# light_scanner_v1_0.net
KiCad netlist of a schematic drawn in EAGLE
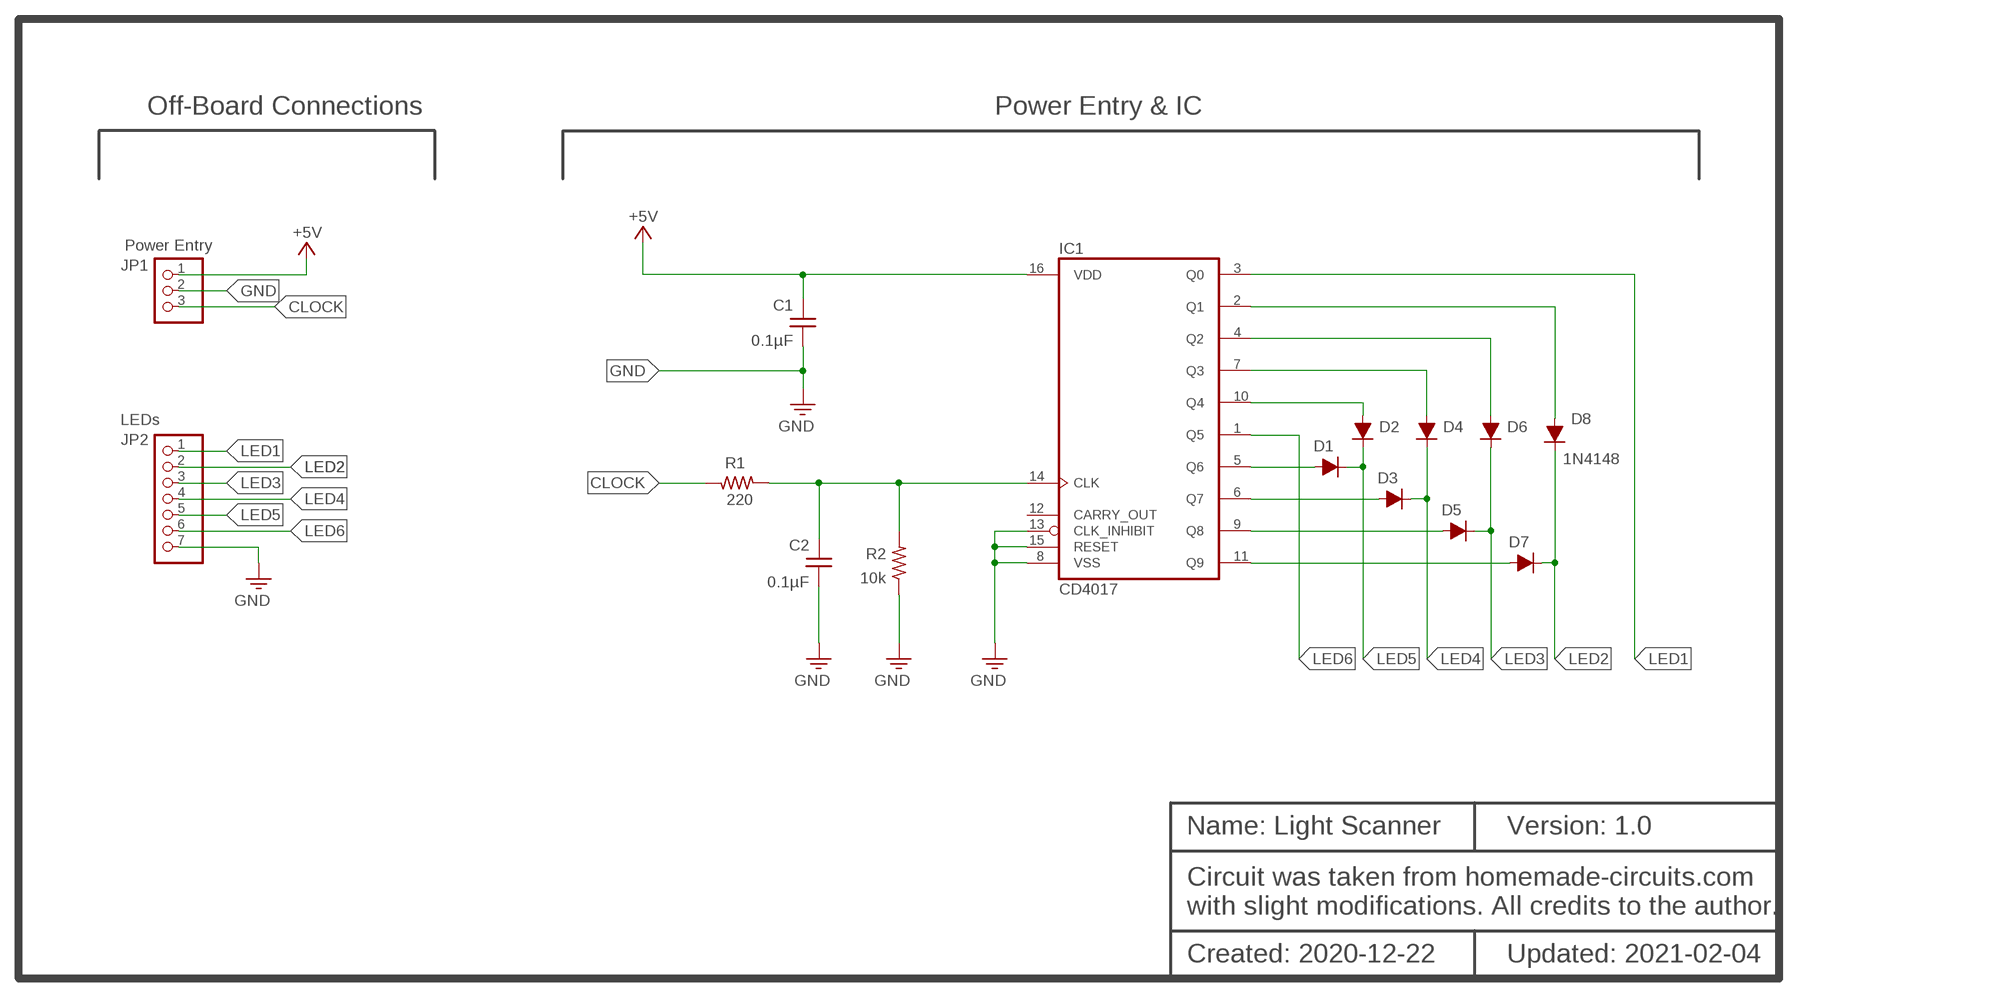
[diagram p0: schematic, sheet 1]

(export (version "E")
  (design (tool "Eeschema 10.0.6"))
  (components
    (comp (ref "C1")
      (value "0.1µF")
      (footprint "eagle-import:C_H5")
      (libsource (lib "eagle-import") (part "C_K104K15X7RF53H5_0.1µF"))
    )
    (comp (ref "C2")
      (value "0.1µF")
      (footprint "eagle-import:C_H5")
      (libsource (lib "eagle-import") (part "C_K104K15X7RF53H5_0.1µF"))
    )
    (comp (ref "D1")
      (value "D_1N4148")
      (footprint "eagle-import:DO35-7A")
      (libsource (lib "eagle-import") (part "D_1N4148"))
    )
    (comp (ref "D2")
      (value "D_1N4148")
      (footprint "eagle-import:DO35-7A")
      (libsource (lib "eagle-import") (part "D_1N4148"))
    )
    (comp (ref "D3")
      (value "D_1N4148")
      (footprint "eagle-import:DO35-7A")
      (libsource (lib "eagle-import") (part "D_1N4148"))
    )
    (comp (ref "D4")
      (value "D_1N4148")
      (footprint "eagle-import:DO35-7A")
      (libsource (lib "eagle-import") (part "D_1N4148"))
    )
    (comp (ref "D5")
      (value "D_1N4148")
      (footprint "eagle-import:DO35-7A")
      (libsource (lib "eagle-import") (part "D_1N4148"))
    )
    (comp (ref "D6")
      (value "D_1N4148")
      (footprint "eagle-import:DO35-7A")
      (libsource (lib "eagle-import") (part "D_1N4148"))
    )
    (comp (ref "D7")
      (value "D_1N4148")
      (footprint "eagle-import:DO35-7A")
      (libsource (lib "eagle-import") (part "D_1N4148"))
    )
    (comp (ref "D8")
      (value "1N4148")
      (footprint "eagle-import:DO35-7A")
      (libsource (lib "eagle-import") (part "D_1N4148"))
    )
    (comp (ref "IC1")
      (value "CD4017")
      (footprint "eagle-import:DIP16")
      (libsource (lib "eagle-import") (part "CD4017"))
    )
    (comp (ref "JP1")
      (value "Power Entry")
      (footprint "eagle-import:1X03")
      (libsource (lib "eagle-import") (part "PINHD-1X3"))
    )
    (comp (ref "JP2")
      (value "LEDs")
      (footprint "eagle-import:1X07")
      (libsource (lib "eagle-import") (part "PINHD-1X7"))
    )
    (comp (ref "R1")
      (value "220")
      (footprint "eagle-import:R_THM")
      (libsource (lib "eagle-import") (part "R_THM"))
    )
    (comp (ref "R2")
      (value "10k")
      (footprint "eagle-import:R_THM")
      (libsource (lib "eagle-import") (part "R_THM"))
    )
  )
  (nets
    (net (code "1") (name "+5V") (class "Default")
      (node (ref "C1") (pin "1") (pinfunction "1_1") (pintype "passive"))
      (node (ref "IC1") (pin "16") (pinfunction "VDD_16") (pintype "bidirectional"))
      (node (ref "JP1") (pin "1") (pinfunction "1_1") (pintype "passive"))
    )
    (net (code "2") (name "CLOCK") (class "Default")
      (node (ref "JP1") (pin "3") (pinfunction "3_3") (pintype "passive"))
      (node (ref "R1") (pin "2") (pinfunction "2_2") (pintype "passive"))
    )
    (net (code "3") (name "GND") (class "Default")
      (node (ref "C1") (pin "2") (pinfunction "2_2") (pintype "passive"))
      (node (ref "C2") (pin "2") (pinfunction "2_2") (pintype "passive"))
      (node (ref "IC1") (pin "13") (pinfunction "CLK_INHIBIT_13") (pintype "input"))
      (node (ref "IC1") (pin "15") (pinfunction "RESET_15") (pintype "input"))
      (node (ref "IC1") (pin "8") (pinfunction "VSS_8") (pintype "bidirectional"))
      (node (ref "JP1") (pin "2") (pinfunction "2_2") (pintype "passive"))
      (node (ref "JP2") (pin "7") (pinfunction "7_7") (pintype "passive"))
      (node (ref "R2") (pin "1") (pinfunction "1_1") (pintype "passive"))
    )
    (net (code "4") (name "LED1") (class "Default")
      (node (ref "IC1") (pin "3") (pinfunction "Q0_3") (pintype "output"))
      (node (ref "JP2") (pin "1") (pinfunction "1_1") (pintype "passive"))
    )
    (net (code "5") (name "LED2") (class "Default")
      (node (ref "D7") (pin "C") (pinfunction "C_C") (pintype "passive"))
      (node (ref "D8") (pin "C") (pinfunction "C_C") (pintype "passive"))
      (node (ref "JP2") (pin "2") (pinfunction "2_2") (pintype "passive"))
    )
    (net (code "6") (name "LED3") (class "Default")
      (node (ref "D5") (pin "C") (pinfunction "C_C") (pintype "passive"))
      (node (ref "D6") (pin "C") (pinfunction "C_C") (pintype "passive"))
      (node (ref "JP2") (pin "3") (pinfunction "3_3") (pintype "passive"))
    )
    (net (code "7") (name "LED4") (class "Default")
      (node (ref "D3") (pin "C") (pinfunction "C_C") (pintype "passive"))
      (node (ref "D4") (pin "C") (pinfunction "C_C") (pintype "passive"))
      (node (ref "JP2") (pin "4") (pinfunction "4_4") (pintype "passive"))
    )
    (net (code "8") (name "LED5") (class "Default")
      (node (ref "D1") (pin "C") (pinfunction "C_C") (pintype "passive"))
      (node (ref "D2") (pin "C") (pinfunction "C_C") (pintype "passive"))
      (node (ref "JP2") (pin "5") (pinfunction "5_5") (pintype "passive"))
    )
    (net (code "9") (name "LED6") (class "Default")
      (node (ref "IC1") (pin "1") (pinfunction "Q5_1") (pintype "output"))
      (node (ref "JP2") (pin "6") (pinfunction "6_6") (pintype "passive"))
    )
    (net (code "10") (name "Net-(IC1-CLK)") (class "Default")
      (node (ref "C2") (pin "1") (pinfunction "1_1") (pintype "passive"))
      (node (ref "IC1") (pin "14") (pinfunction "CLK_14") (pintype "input"))
      (node (ref "R1") (pin "1") (pinfunction "1_1") (pintype "passive"))
      (node (ref "R2") (pin "2") (pinfunction "2_2") (pintype "passive"))
    )
    (net (code "11") (name "Net-(IC1-Q1)") (class "Default")
      (node (ref "D8") (pin "A") (pinfunction "A_A") (pintype "passive"))
      (node (ref "IC1") (pin "2") (pinfunction "Q1_2") (pintype "output"))
    )
    (net (code "12") (name "Net-(IC1-Q2)") (class "Default")
      (node (ref "D6") (pin "A") (pinfunction "A_A") (pintype "passive"))
      (node (ref "IC1") (pin "4") (pinfunction "Q2_4") (pintype "output"))
    )
    (net (code "13") (name "Net-(IC1-Q3)") (class "Default")
      (node (ref "D4") (pin "A") (pinfunction "A_A") (pintype "passive"))
      (node (ref "IC1") (pin "7") (pinfunction "Q3_7") (pintype "output"))
    )
    (net (code "14") (name "Net-(IC1-Q4)") (class "Default")
      (node (ref "D2") (pin "A") (pinfunction "A_A") (pintype "passive"))
      (node (ref "IC1") (pin "10") (pinfunction "Q4_10") (pintype "output"))
    )
    (net (code "15") (name "Net-(IC1-Q6)") (class "Default")
      (node (ref "D1") (pin "A") (pinfunction "A_A") (pintype "passive"))
      (node (ref "IC1") (pin "5") (pinfunction "Q6_5") (pintype "output"))
    )
    (net (code "16") (name "Net-(IC1-Q7)") (class "Default")
      (node (ref "D3") (pin "A") (pinfunction "A_A") (pintype "passive"))
      (node (ref "IC1") (pin "6") (pinfunction "Q7_6") (pintype "output"))
    )
    (net (code "17") (name "Net-(IC1-Q8)") (class "Default")
      (node (ref "D5") (pin "A") (pinfunction "A_A") (pintype "passive"))
      (node (ref "IC1") (pin "9") (pinfunction "Q8_9") (pintype "output"))
    )
    (net (code "18") (name "Net-(IC1-Q9)") (class "Default")
      (node (ref "D7") (pin "A") (pinfunction "A_A") (pintype "passive"))
      (node (ref "IC1") (pin "11") (pinfunction "Q9_11") (pintype "output"))
    )
    (net (code "19") (name "unconnected-(IC1-CARRY_OUT-Pad12)") (class "Default")
      (node (ref "IC1") (pin "12") (pinfunction "CARRY_OUT_12") (pintype "output"))
    )
  )
)
